# Peripherals.net
KiCad netlist of a schematic drawn in Altium Designer
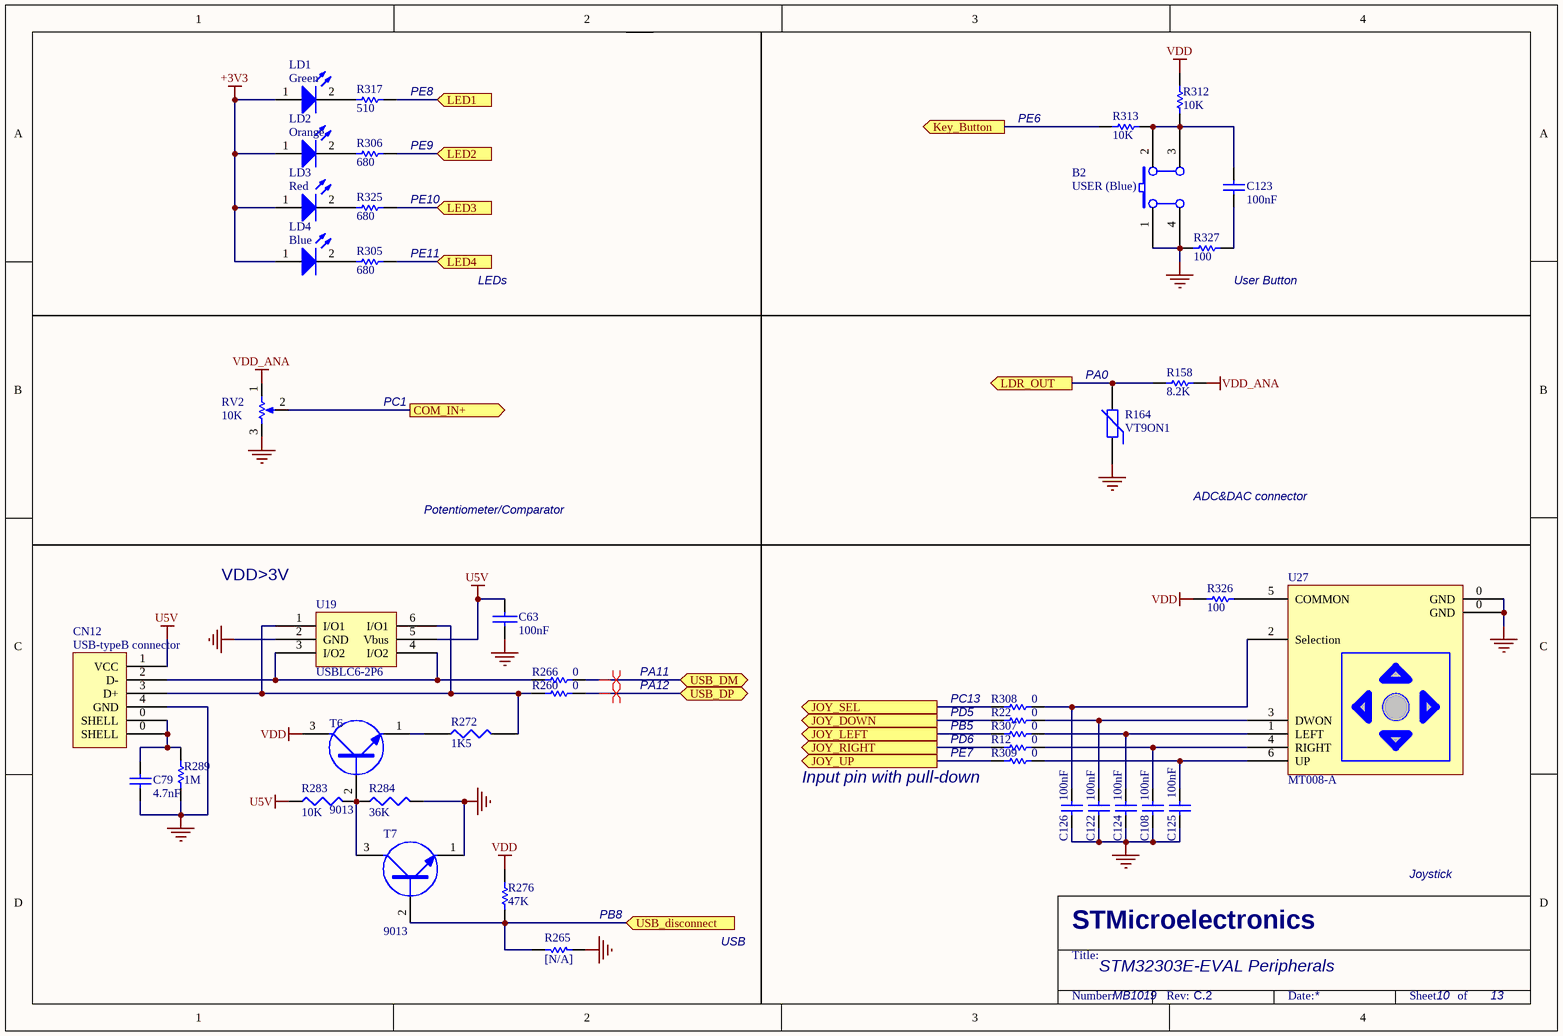
[diagram p0: Peripherals.SchDoc]

(export (version "E")
  (design (tool "Eeschema 10.0.6"))
  (components
    (comp (ref "B2")
      (value "USER (Blue)")
      (footprint "PB10")
      (description "SE PUSHBUTTON")
      (libsource (lib "Documents") (part "SW PUSHBUTTON"))
    )
    (comp (ref "C63")
      (value "100nF")
      (footprint "0603C")
      (description "Capacitor")
      (libsource (lib "*") (part "CAP"))
    )
    (comp (ref "C79")
      (value "4.7nF")
      (footprint "0603C")
      (description "Capacitor")
      (fields (field (name "PUBLISHER") "Altium Limited"))
      (libsource (lib "Miscellaneous Devices") (part "CAP"))
    )
    (comp (ref "C108")
      (value "100nF")
      (footprint "0603C")
      (description "Capacitor")
      (fields (field (name "PUBLISHER") "Altium Limited"))
      (libsource (lib "Miscellaneous Devices") (part "CAP"))
    )
    (comp (ref "C122")
      (value "100nF")
      (footprint "0603C")
      (description "Capacitor")
      (fields (field (name "PUBLISHER") "Altium Limited"))
      (libsource (lib "Miscellaneous Devices") (part "CAP"))
    )
    (comp (ref "C123")
      (value "100nF")
      (footprint "0603C")
      (description "Capacitor")
      (fields (field (name "PUBLISHER") "Altium Limited"))
      (libsource (lib "Miscellaneous Devices") (part "CAP"))
    )
    (comp (ref "C124")
      (value "100nF")
      (footprint "0603C")
      (description "Capacitor")
      (fields (field (name "PUBLISHER") "Altium Limited"))
      (libsource (lib "Miscellaneous Devices") (part "CAP"))
    )
    (comp (ref "C125")
      (value "100nF")
      (footprint "0603C")
      (description "Capacitor")
      (fields (field (name "PUBLISHER") "Altium Limited"))
      (libsource (lib "Miscellaneous Devices") (part "CAP"))
    )
    (comp (ref "C126")
      (value "100nF")
      (footprint "0603C")
      (description "Capacitor")
      (fields (field (name "PUBLISHER") "Altium Limited"))
      (libsource (lib "Miscellaneous Devices") (part "CAP"))
    )
    (comp (ref "CN12")
      (value "USB-typeB connector")
      (footprint "USB-B")
      (description "USB-B")
      (libsource (lib "Documents") (part "USB-B"))
    )
    (comp (ref "LD1")
      (value "Green")
      (footprint "0603D")
      (description "Typical RED, GREEN, YELLOW, AMBER GaAs LED")
      (fields (field (name "PUBLISHER") "Altium Limited"))
      (libsource (lib "Miscellaneous Devices") (part "LED2"))
    )
    (comp (ref "LD2")
      (value "Orange")
      (footprint "0603D")
      (description "Typical RED, GREEN, YELLOW, AMBER GaAs LED")
      (fields (field (name "PUBLISHER") "Altium Limited"))
      (libsource (lib "Miscellaneous Devices") (part "LED2"))
    )
    (comp (ref "LD3")
      (value "Red")
      (footprint "0603D")
      (description "Typical RED, GREEN, YELLOW, AMBER GaAs LED")
      (fields (field (name "PUBLISHER") "Altium Limited"))
      (libsource (lib "Miscellaneous Devices") (part "LED2"))
    )
    (comp (ref "LD4")
      (value "Blue")
      (footprint "0603D")
      (description "Typical RED, GREEN, YELLOW, AMBER GaAs LED")
      (fields (field (name "PUBLISHER") "Altium Limited"))
      (libsource (lib "Miscellaneous Devices") (part "LED2"))
    )
    (comp (ref "R12")
      (value "0")
      (footprint "0603R")
      (description "Resistor")
      (fields (field (name "PUBLISHER") "Altium Limited"))
      (libsource (lib "Miscellaneous Devices") (part "Res1"))
    )
    (comp (ref "R22")
      (value "0")
      (footprint "0603R")
      (description "Resistor")
      (fields (field (name "PUBLISHER") "Altium Limited"))
      (libsource (lib "Miscellaneous Devices") (part "Res1"))
    )
    (comp (ref "R158")
      (value "8.2K")
      (footprint "0603R")
      (description "Resistor")
      (fields (field (name "PUBLISHER") "Altium Limited"))
      (libsource (lib "Miscellaneous Devices") (part "Res1"))
    )
    (comp (ref "R164")
      (value "VT9ON1")
      (footprint "PVT901")
      (description "Varistor (Voltage-Sensitive Resistor)")
      (fields (field (name "PUBLISHER") "Altium Limited"))
      (libsource (lib "Miscellaneous Devices") (part "Res Varistor"))
    )
    (comp (ref "R260")
      (value "0")
      (footprint "0603R")
      (description "Resistor")
      (fields (field (name "PUBLISHER") "Altium Limited"))
      (libsource (lib "Miscellaneous Devices") (part "Res1"))
    )
    (comp (ref "R265")
      (value "[N/A]")
      (footprint "0603R")
      (description "Resistor")
      (fields (field (name "PUBLISHER") "Altium Limited"))
      (libsource (lib "Miscellaneous Devices") (part "Res1"))
    )
    (comp (ref "R266")
      (value "0")
      (footprint "0603R")
      (description "Resistor")
      (fields (field (name "PUBLISHER") "Altium Limited"))
      (libsource (lib "Miscellaneous Devices") (part "Res1"))
    )
    (comp (ref "R272") (value "1K5") (footprint "0603R") (libsource (lib "*") (part "RES1")))
    (comp (ref "R276")
      (value "47K")
      (footprint "0603R")
      (description "Resistor")
      (fields (field (name "PUBLISHER") "Altium Limited"))
      (libsource (lib "Miscellaneous Devices") (part "Res1"))
    )
    (comp (ref "R283") (value "10K") (footprint "0603R") (libsource (lib "*") (part "R")))
    (comp (ref "R284") (value "36K") (footprint "0603R") (libsource (lib "*") (part "R")))
    (comp (ref "R289")
      (value "1M")
      (footprint "0603R")
      (description "Resistor")
      (fields (field (name "PUBLISHER") "Altium Limited"))
      (libsource (lib "Miscellaneous Devices") (part "Res1"))
    )
    (comp (ref "R305")
      (value "680")
      (footprint "0603R")
      (description "Resistor")
      (fields (field (name "PUBLISHER") "Altium Limited"))
      (libsource (lib "Miscellaneous Devices") (part "Res1"))
    )
    (comp (ref "R306")
      (value "680")
      (footprint "0603R")
      (description "Resistor")
      (fields (field (name "PUBLISHER") "Altium Limited"))
      (libsource (lib "Miscellaneous Devices") (part "Res1"))
    )
    (comp (ref "R307")
      (value "0")
      (footprint "0603R")
      (description "Resistor")
      (fields (field (name "PUBLISHER") "Altium Limited"))
      (libsource (lib "Miscellaneous Devices") (part "Res1"))
    )
    (comp (ref "R308")
      (value "0")
      (footprint "0603R")
      (description "Resistor")
      (fields (field (name "PUBLISHER") "Altium Limited"))
      (libsource (lib "Miscellaneous Devices") (part "Res1"))
    )
    (comp (ref "R309")
      (value "0")
      (footprint "0603R")
      (description "Resistor")
      (fields (field (name "PUBLISHER") "Altium Limited"))
      (libsource (lib "Miscellaneous Devices") (part "Res1"))
    )
    (comp (ref "R312")
      (value "10K")
      (footprint "0603R")
      (description "Resistor")
      (fields (field (name "PUBLISHER") "Altium Limited"))
      (libsource (lib "Miscellaneous Devices") (part "res1"))
    )
    (comp (ref "R313")
      (value "10K")
      (footprint "0603R")
      (description "Resistor")
      (fields (field (name "PUBLISHER") "Altium Limited"))
      (libsource (lib "Miscellaneous Devices") (part "Res1"))
    )
    (comp (ref "R317")
      (value "510")
      (footprint "0603R")
      (description "Resistor")
      (fields (field (name "PUBLISHER") "Altium Limited"))
      (libsource (lib "Miscellaneous Devices") (part "Res1"))
    )
    (comp (ref "R325")
      (value "680")
      (footprint "0603R")
      (description "Resistor")
      (fields (field (name "PUBLISHER") "Altium Limited"))
      (libsource (lib "Miscellaneous Devices") (part "Res1"))
    )
    (comp (ref "R326")
      (value "100")
      (footprint "0603R")
      (description "Resistor")
      (fields (field (name "PUBLISHER") "Altium Limited"))
      (libsource (lib "Miscellaneous Devices") (part "Res1"))
    )
    (comp (ref "R327")
      (value "100")
      (footprint "0603R")
      (description "Resistor")
      (fields (field (name "PUBLISHER") "Altium Limited"))
      (libsource (lib "Miscellaneous Devices") (part "Res1"))
    )
    (comp (ref "RV2") (value "10K") (footprint "3296W") (libsource (lib "STR910_SCHLIB") (part "RV")))
    (comp (ref "T6") (value "9013") (footprint "SOT-23") (libsource (lib "*") (part "NPN")))
    (comp (ref "T7") (value "9013") (footprint "SOT-23") (libsource (lib "*") (part "NPN")))
    (comp (ref "U19")
      (value "USBLC6-2P6")
      (footprint "SOT-666")
      (libsource (lib "STR910_SCHLIB") (part "USBLC6-2"))
    )
    (comp (ref "U27") (value "MT008-A") (footprint "JOY") (libsource (lib "MB988") (part "MT-008A")))
  )
  (nets
    (net (code "1") (name "+3V3") (class "Default")
      (node (ref "LD1") (pin "1") (pinfunction "A_1") (pintype "passive"))
      (node (ref "LD2") (pin "1") (pinfunction "A_1") (pintype "passive"))
      (node (ref "LD3") (pin "1") (pinfunction "A_1") (pintype "passive"))
      (node (ref "LD4") (pin "1") (pinfunction "A_1") (pintype "passive"))
    )
    (net (code "2") (name "/COM_IN+") (class "Default")
      (node (ref "RV2") (pin "2") (pinfunction "TAP_2") (pintype "passive"))
    )
    (net (code "3") (name "/JOY_DOWN") (class "Default")
      (node (ref "R22") (pin "1") (pinfunction "1_1") (pintype "passive"))
    )
    (net (code "4") (name "/JOY_LEFT") (class "Default")
      (node (ref "R307") (pin "2") (pinfunction "2_2") (pintype "passive"))
    )
    (net (code "5") (name "/JOY_RIGHT") (class "Default")
      (node (ref "R12") (pin "1") (pinfunction "1_1") (pintype "passive"))
    )
    (net (code "6") (name "/JOY_SEL") (class "Default")
      (node (ref "R308") (pin "2") (pinfunction "2_2") (pintype "passive"))
    )
    (net (code "7") (name "/JOY_UP") (class "Default")
      (node (ref "R309") (pin "2") (pinfunction "2_2") (pintype "passive"))
    )
    (net (code "8") (name "/Key_Button") (class "Default")
      (node (ref "R313") (pin "2") (pinfunction "2_2") (pintype "passive"))
    )
    (net (code "9") (name "/LDR_OUT") (class "Default")
      (node (ref "R158") (pin "1") (pinfunction "1_1") (pintype "passive"))
      (node (ref "R164") (pin "2") (pinfunction "2_2") (pintype "passive"))
    )
    (net (code "10") (name "/LED1") (class "Default")
      (node (ref "R317") (pin "1") (pinfunction "1_1") (pintype "passive"))
    )
    (net (code "11") (name "/LED2") (class "Default")
      (node (ref "R306") (pin "1") (pinfunction "1_1") (pintype "passive"))
    )
    (net (code "12") (name "/LED3") (class "Default")
      (node (ref "R325") (pin "1") (pinfunction "1_1") (pintype "passive"))
    )
    (net (code "13") (name "/LED4") (class "Default")
      (node (ref "R305") (pin "1") (pinfunction "1_1") (pintype "passive"))
    )
    (net (code "14") (name "/USB_DM") (class "Default")
      (node (ref "R266") (pin "1") (pinfunction "1_1") (pintype "passive"))
    )
    (net (code "15") (name "/USB_DP") (class "Default")
      (node (ref "R260") (pin "1") (pinfunction "1_1") (pintype "passive"))
    )
    (net (code "16") (name "/USB_disconnect") (class "Default")
      (node (ref "R265") (pin "2") (pinfunction "2_2") (pintype "passive"))
      (node (ref "R276") (pin "1") (pinfunction "1_1") (pintype "passive"))
      (node (ref "T7") (pin "2") (pinfunction "B_2") (pintype "passive"))
    )
    (net (code "17") (name "GND") (class "Default")
      (node (ref "B2") (pin "1") (pinfunction "A0_1") (pintype "passive"))
      (node (ref "B2") (pin "4") (pinfunction "A1_4") (pintype "passive"))
      (node (ref "C108") (pin "1") (pinfunction "1_1") (pintype "passive"))
      (node (ref "C122") (pin "1") (pinfunction "1_1") (pintype "passive"))
      (node (ref "C124") (pin "1") (pinfunction "1_1") (pintype "passive"))
      (node (ref "C125") (pin "1") (pinfunction "1_1") (pintype "passive"))
      (node (ref "C126") (pin "1") (pinfunction "1_1") (pintype "passive"))
      (node (ref "C63") (pin "2") (pinfunction "2_2") (pintype "passive"))
      (node (ref "C79") (pin "1") (pinfunction "1_1") (pintype "passive"))
      (node (ref "CN12") (pin "4") (pinfunction "GND_4") (pintype "passive"))
      (node (ref "R164") (pin "1") (pinfunction "1_1") (pintype "passive"))
      (node (ref "R265") (pin "1") (pinfunction "1_1") (pintype "passive"))
      (node (ref "R284") (pin "2") (pinfunction "2_2") (pintype "passive"))
      (node (ref "R289") (pin "1") (pinfunction "1_1") (pintype "passive"))
      (node (ref "R327") (pin "1") (pinfunction "1_1") (pintype "passive"))
      (node (ref "RV2") (pin "3") (pinfunction "TOP_3") (pintype "passive"))
      (node (ref "T7") (pin "1") (pinfunction "E_1") (pintype "passive"))
      (node (ref "U19") (pin "2") (pinfunction "GND_2") (pintype "passive"))
      (node (ref "U27") (pin "0") (pinfunction "GND_0") (pintype "passive"))
    )
    (net (code "18") (name "Net-(B2-B0)") (class "Default")
      (node (ref "B2") (pin "2") (pinfunction "B0_2") (pintype "passive"))
      (node (ref "B2") (pin "3") (pinfunction "B1_3") (pintype "passive"))
      (node (ref "C123") (pin "2") (pinfunction "2_2") (pintype "passive"))
      (node (ref "R312") (pin "1") (pinfunction "1_1") (pintype "passive"))
      (node (ref "R313") (pin "1") (pinfunction "1_1") (pintype "passive"))
    )
    (net (code "19") (name "Net-(C123-Pad1)") (class "Default")
      (node (ref "C123") (pin "1") (pinfunction "1_1") (pintype "passive"))
      (node (ref "R327") (pin "2") (pinfunction "2_2") (pintype "passive"))
    )
    (net (code "20") (name "Net-(CN12-D+)") (class "Default")
      (node (ref "CN12") (pin "3") (pinfunction "D+_3") (pintype "passive"))
      (node (ref "R260") (pin "2") (pinfunction "2_2") (pintype "passive"))
      (node (ref "R272") (pin "2") (pinfunction "2_2") (pintype "passive"))
      (node (ref "U19") (pin "1") (pinfunction "I/O1_1") (pintype "passive"))
      (node (ref "U19") (pin "6") (pinfunction "I/O1_6") (pintype "passive"))
    )
    (net (code "21") (name "Net-(CN12-D-)") (class "Default")
      (node (ref "CN12") (pin "2") (pinfunction "D-_2") (pintype "passive"))
      (node (ref "R266") (pin "2") (pinfunction "2_2") (pintype "passive"))
      (node (ref "U19") (pin "3") (pinfunction "I/O2_3") (pintype "passive"))
      (node (ref "U19") (pin "4") (pinfunction "I/O2_4") (pintype "passive"))
    )
    (net (code "22") (name "Net-(CN12-SHELL)") (class "Default")
      (node (ref "C79") (pin "2") (pinfunction "2_2") (pintype "passive"))
      (node (ref "CN12") (pin "0") (pinfunction "SHELL_0") (pintype "passive"))
      (node (ref "R289") (pin "2") (pinfunction "2_2") (pintype "passive"))
    )
    (net (code "23") (name "Net-(LD1-K)") (class "Default")
      (node (ref "LD1") (pin "2") (pinfunction "K_2") (pintype "passive"))
      (node (ref "R317") (pin "2") (pinfunction "2_2") (pintype "passive"))
    )
    (net (code "24") (name "Net-(LD2-K)") (class "Default")
      (node (ref "LD2") (pin "2") (pinfunction "K_2") (pintype "passive"))
      (node (ref "R306") (pin "2") (pinfunction "2_2") (pintype "passive"))
    )
    (net (code "25") (name "Net-(LD3-K)") (class "Default")
      (node (ref "LD3") (pin "2") (pinfunction "K_2") (pintype "passive"))
      (node (ref "R325") (pin "2") (pinfunction "2_2") (pintype "passive"))
    )
    (net (code "26") (name "Net-(LD4-K)") (class "Default")
      (node (ref "LD4") (pin "2") (pinfunction "K_2") (pintype "passive"))
      (node (ref "R305") (pin "2") (pinfunction "2_2") (pintype "passive"))
    )
    (net (code "27") (name "Net-(T6-B)") (class "Default")
      (node (ref "R283") (pin "2") (pinfunction "2_2") (pintype "passive"))
      (node (ref "R284") (pin "1") (pinfunction "1_1") (pintype "passive"))
      (node (ref "T6") (pin "2") (pinfunction "B_2") (pintype "passive"))
      (node (ref "T7") (pin "3") (pinfunction "C_3") (pintype "passive"))
    )
    (net (code "28") (name "Net-(T6-E)") (class "Default")
      (node (ref "R272") (pin "1") (pinfunction "1_1") (pintype "passive"))
      (node (ref "T6") (pin "1") (pinfunction "E_1") (pintype "passive"))
    )
    (net (code "29") (name "Net-(U27-COMMON)") (class "Default")
      (node (ref "R326") (pin "2") (pinfunction "2_2") (pintype "passive"))
      (node (ref "U27") (pin "5") (pinfunction "COMMON_5") (pintype "passive"))
    )
    (net (code "30") (name "Net-(U27-DWON)") (class "Default")
      (node (ref "C122") (pin "2") (pinfunction "2_2") (pintype "passive"))
      (node (ref "R22") (pin "2") (pinfunction "2_2") (pintype "passive"))
      (node (ref "U27") (pin "3") (pinfunction "DWON_3") (pintype "passive"))
    )
    (net (code "31") (name "Net-(U27-LEFT)") (class "Default")
      (node (ref "C124") (pin "2") (pinfunction "2_2") (pintype "passive"))
      (node (ref "R307") (pin "1") (pinfunction "1_1") (pintype "passive"))
      (node (ref "U27") (pin "1") (pinfunction "LEFT_1") (pintype "passive"))
    )
    (net (code "32") (name "Net-(U27-RIGHT)") (class "Default")
      (node (ref "C108") (pin "2") (pinfunction "2_2") (pintype "passive"))
      (node (ref "R12") (pin "2") (pinfunction "2_2") (pintype "passive"))
      (node (ref "U27") (pin "4") (pinfunction "RIGHT_4") (pintype "passive"))
    )
    (net (code "33") (name "Net-(U27-Selection)") (class "Default")
      (node (ref "C126") (pin "2") (pinfunction "2_2") (pintype "passive"))
      (node (ref "R308") (pin "1") (pinfunction "1_1") (pintype "passive"))
      (node (ref "U27") (pin "2") (pinfunction "Selection_2") (pintype "passive"))
    )
    (net (code "34") (name "Net-(U27-UP)") (class "Default")
      (node (ref "C125") (pin "2") (pinfunction "2_2") (pintype "passive"))
      (node (ref "R309") (pin "1") (pinfunction "1_1") (pintype "passive"))
      (node (ref "U27") (pin "6") (pinfunction "UP_6") (pintype "passive"))
    )
    (net (code "35") (name "U5V") (class "Default")
      (node (ref "C63") (pin "1") (pinfunction "1_1") (pintype "passive"))
      (node (ref "CN12") (pin "1") (pinfunction "VCC_1") (pintype "passive"))
      (node (ref "R283") (pin "1") (pinfunction "1_1") (pintype "passive"))
      (node (ref "U19") (pin "5") (pinfunction "Vbus_5") (pintype "passive"))
    )
    (net (code "36") (name "VDD") (class "Default")
      (node (ref "R276") (pin "2") (pinfunction "2_2") (pintype "passive"))
      (node (ref "R312") (pin "2") (pinfunction "2_2") (pintype "passive"))
      (node (ref "R326") (pin "1") (pinfunction "1_1") (pintype "passive"))
      (node (ref "T6") (pin "3") (pinfunction "C_3") (pintype "passive"))
    )
    (net (code "37") (name "VDD_ANA") (class "Default")
      (node (ref "R158") (pin "2") (pinfunction "2_2") (pintype "passive"))
      (node (ref "RV2") (pin "1") (pinfunction "BOT_1") (pintype "passive"))
    )
  )
)
